# CanBus20mar.net
KiCad netlist of a schematic drawn in EAGLE
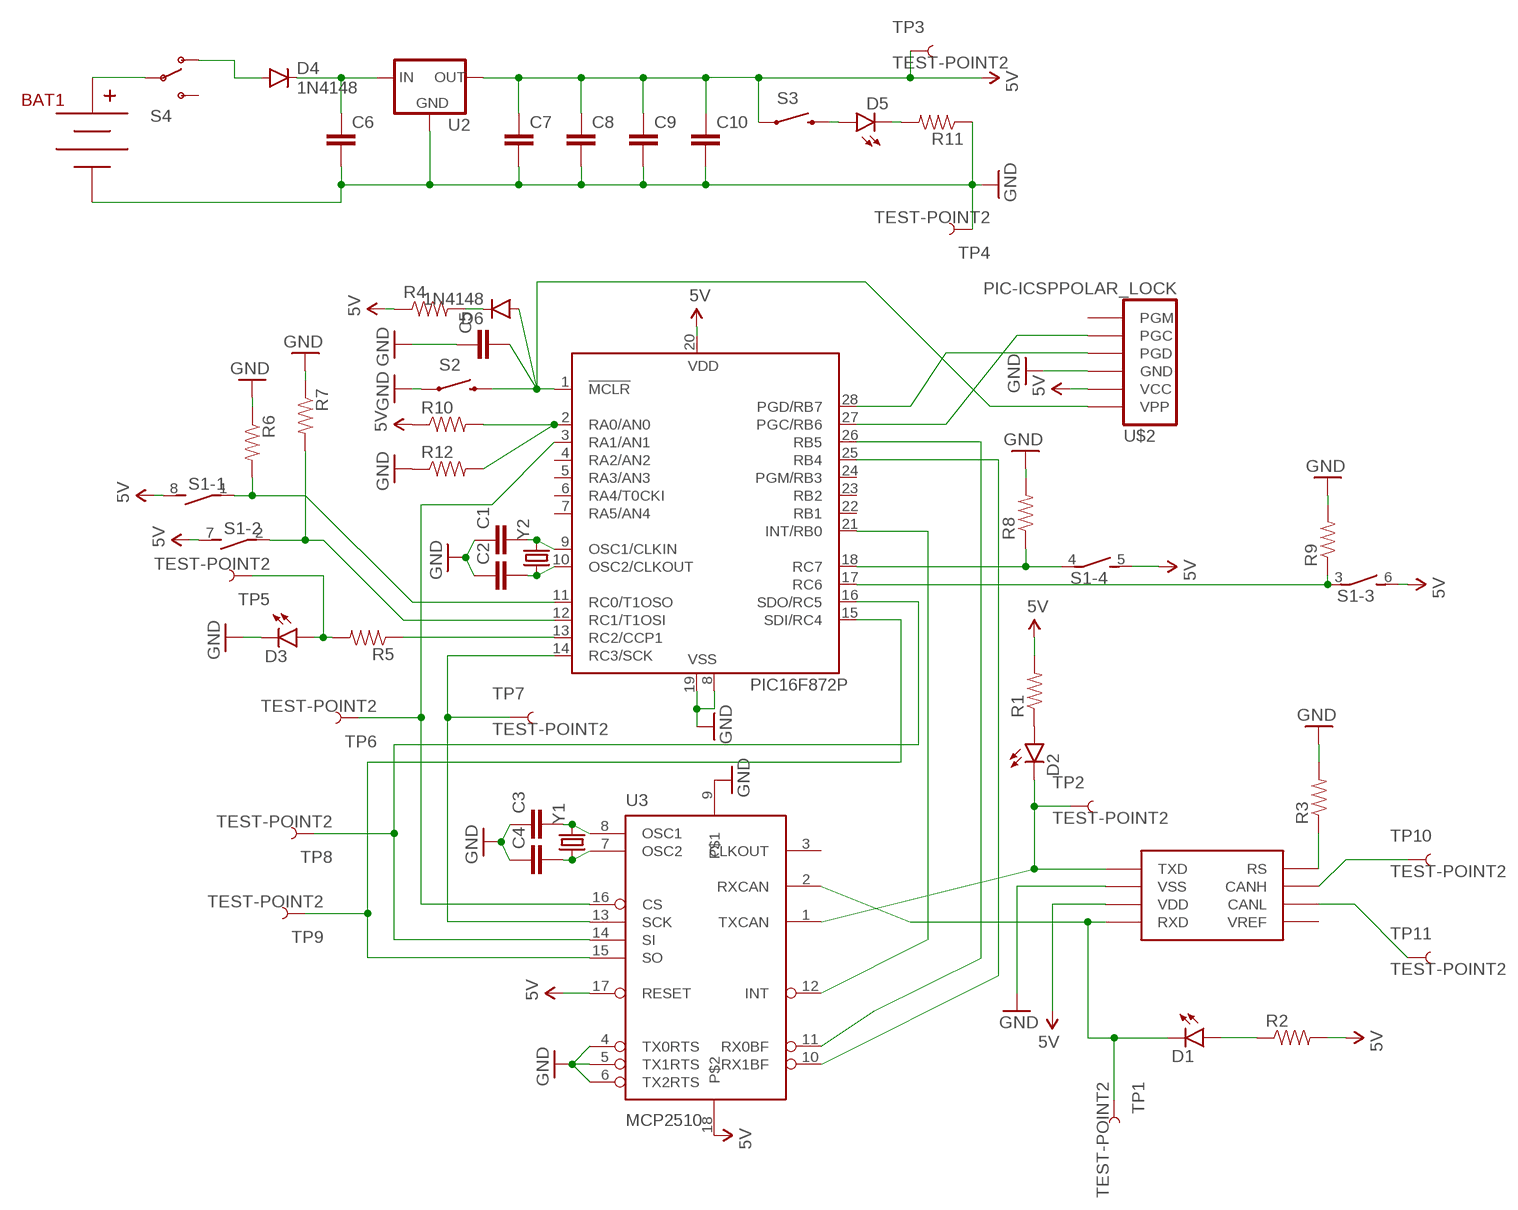
[diagram p0: schematic, sheet 1]

(export (version "E")
  (design (tool "Eeschema 10.0.6"))
  (components
    (comp (ref "BAT1")
      (value "BC9VPC")
      (footprint "eagle-import:BC9VPC")
      (libsource (lib "eagle-import") (part "BC9VPC"))
    )
    (comp (ref "C1")
      (value "CAPPTH")
      (footprint "eagle-import:CAP-PTH-SMALL")
      (libsource (lib "eagle-import") (part "CAPPTH"))
    )
    (comp (ref "C2")
      (value "CAPPTH")
      (footprint "eagle-import:CAP-PTH-SMALL")
      (libsource (lib "eagle-import") (part "CAPPTH"))
    )
    (comp (ref "C3")
      (value "CAPPTH")
      (footprint "eagle-import:CAP-PTH-SMALL")
      (libsource (lib "eagle-import") (part "CAPPTH"))
    )
    (comp (ref "C4")
      (value "CAPPTH")
      (footprint "eagle-import:CAP-PTH-SMALL")
      (libsource (lib "eagle-import") (part "CAPPTH"))
    )
    (comp (ref "C5")
      (value "CAPPTH")
      (footprint "eagle-import:CAP-PTH-SMALL")
      (libsource (lib "eagle-import") (part "CAPPTH"))
    )
    (comp (ref "C6")
      (value "CAPPTH")
      (footprint "eagle-import:CAP-PTH-SMALL")
      (libsource (lib "eagle-import") (part "CAPPTH"))
    )
    (comp (ref "C7")
      (value "CAPPTH")
      (footprint "eagle-import:CAP-PTH-SMALL")
      (libsource (lib "eagle-import") (part "CAPPTH"))
    )
    (comp (ref "C8")
      (value "CAPPTH")
      (footprint "eagle-import:CAP-PTH-SMALL")
      (libsource (lib "eagle-import") (part "CAPPTH"))
    )
    (comp (ref "C9")
      (value "CAPPTH")
      (footprint "eagle-import:CAP-PTH-SMALL")
      (libsource (lib "eagle-import") (part "CAPPTH"))
    )
    (comp (ref "C10")
      (value "CAPPTH")
      (footprint "eagle-import:CAP-PTH-SMALL")
      (libsource (lib "eagle-import") (part "CAPPTH"))
    )
    (comp (ref "D1")
      (value "LED5MM")
      (footprint "eagle-import:LED5MM")
      (libsource (lib "eagle-import") (part "LED5MM"))
    )
    (comp (ref "D2")
      (value "LED5MM")
      (footprint "eagle-import:LED5MM")
      (libsource (lib "eagle-import") (part "LED5MM"))
    )
    (comp (ref "D3")
      (value "LED5MM")
      (footprint "eagle-import:LED5MM")
      (libsource (lib "eagle-import") (part "LED5MM"))
    )
    (comp (ref "D4")
      (value "1N4148")
      (footprint "eagle-import:DIODE-1N4148-KIT")
      (libsource (lib "eagle-import") (part "DIODEKIT"))
    )
    (comp (ref "D5")
      (value "LED5MM")
      (footprint "eagle-import:LED5MM")
      (libsource (lib "eagle-import") (part "LED5MM"))
    )
    (comp (ref "D6")
      (value "1N4148")
      (footprint "eagle-import:DIODE-1N4148-KIT")
      (libsource (lib "eagle-import") (part "DIODEKIT"))
    )
    (comp (ref "IC1")
      (value "PIC16F872P")
      (footprint "eagle-import:DIL28-3")
      (fields (field (name "MF") "MICROCHIP") (field (name "MPN") "PIC16F872-I/SP"))
      (libsource (lib "eagle-import") (part "PIC16872PF"))
    )
    (comp (ref "R1")
      (value "RESISTOREZ")
      (footprint "eagle-import:AXIAL-0.3EZ")
      (libsource (lib "eagle-import") (part "RESISTOREZ"))
    )
    (comp (ref "R2")
      (value "RESISTOREZ")
      (footprint "eagle-import:AXIAL-0.3EZ")
      (libsource (lib "eagle-import") (part "RESISTOREZ"))
    )
    (comp (ref "R3")
      (value "RESISTOREZ")
      (footprint "eagle-import:AXIAL-0.3EZ")
      (libsource (lib "eagle-import") (part "RESISTOREZ"))
    )
    (comp (ref "R4")
      (value "RESISTOREZ")
      (footprint "eagle-import:AXIAL-0.3EZ")
      (libsource (lib "eagle-import") (part "RESISTOREZ"))
    )
    (comp (ref "R5")
      (value "RESISTOREZ")
      (footprint "eagle-import:AXIAL-0.3EZ")
      (libsource (lib "eagle-import") (part "RESISTOREZ"))
    )
    (comp (ref "R6")
      (value "RESISTOREZ")
      (footprint "eagle-import:AXIAL-0.3EZ")
      (libsource (lib "eagle-import") (part "RESISTOREZ"))
    )
    (comp (ref "R7")
      (value "RESISTOREZ")
      (footprint "eagle-import:AXIAL-0.3EZ")
      (libsource (lib "eagle-import") (part "RESISTOREZ"))
    )
    (comp (ref "R8")
      (value "RESISTOREZ")
      (footprint "eagle-import:AXIAL-0.3EZ")
      (libsource (lib "eagle-import") (part "RESISTOREZ"))
    )
    (comp (ref "R9")
      (value "RESISTOREZ")
      (footprint "eagle-import:AXIAL-0.3EZ")
      (libsource (lib "eagle-import") (part "RESISTOREZ"))
    )
    (comp (ref "R10")
      (value "RESISTOREZ")
      (footprint "eagle-import:AXIAL-0.3EZ")
      (libsource (lib "eagle-import") (part "RESISTOREZ"))
    )
    (comp (ref "R11")
      (value "RESISTOREZ")
      (footprint "eagle-import:AXIAL-0.3EZ")
      (libsource (lib "eagle-import") (part "RESISTOREZ"))
    )
    (comp (ref "R12")
      (value "RESISTORAXIAL-0.3")
      (footprint "eagle-import:AXIAL-0.3")
      (libsource (lib "eagle-import") (part "SparkFun-Resistors_RESISTORAXIAL-0.3"))
    )
    (comp (ref "S1")
      (value "DIP04S")
      (footprint "eagle-import:DIP04S")
      (libsource (lib "eagle-import") (part "DIP04S"))
    )
    (comp (ref "S2")
      (value "SWITCH-MOMENTARY-2PTH")
      (footprint "eagle-import:TACTILE-PTH")
      (libsource (lib "eagle-import") (part "SWITCH-MOMENTARY-2PTH"))
    )
    (comp (ref "S3")
      (value "SWITCH-MOMENTARY-2PTH")
      (footprint "eagle-import:TACTILE-PTH")
      (libsource (lib "eagle-import") (part "SWITCH-MOMENTARY-2PTH"))
    )
    (comp (ref "S4")
      (value "SWITCH-SPDTSMD2")
      (footprint "eagle-import:SWITCH-SPDT-SMD")
      (libsource (lib "eagle-import") (part "SWITCH-SPDTSMD2"))
    )
    (comp (ref "TP1")
      (value "TEST-POINT2")
      (footprint "eagle-import:PAD.02X.02")
      (libsource (lib "eagle-import") (part "TEST-POINT2"))
    )
    (comp (ref "TP2")
      (value "TEST-POINT2")
      (footprint "eagle-import:PAD.02X.02")
      (libsource (lib "eagle-import") (part "TEST-POINT2"))
    )
    (comp (ref "TP3")
      (value "TEST-POINT2")
      (footprint "eagle-import:PAD.02X.02")
      (libsource (lib "eagle-import") (part "TEST-POINT2"))
    )
    (comp (ref "TP4")
      (value "TEST-POINT2")
      (footprint "eagle-import:PAD.02X.02")
      (libsource (lib "eagle-import") (part "TEST-POINT2"))
    )
    (comp (ref "TP5")
      (value "TEST-POINT2")
      (footprint "eagle-import:PAD.02X.02")
      (libsource (lib "eagle-import") (part "TEST-POINT2"))
    )
    (comp (ref "TP6")
      (value "TEST-POINT2")
      (footprint "eagle-import:PAD.02X.02")
      (libsource (lib "eagle-import") (part "TEST-POINT2"))
    )
    (comp (ref "TP7")
      (value "TEST-POINT2")
      (footprint "eagle-import:PAD.02X.02")
      (libsource (lib "eagle-import") (part "TEST-POINT2"))
    )
    (comp (ref "TP8")
      (value "TEST-POINT2")
      (footprint "eagle-import:PAD.02X.02")
      (libsource (lib "eagle-import") (part "TEST-POINT2"))
    )
    (comp (ref "TP9")
      (value "TEST-POINT2")
      (footprint "eagle-import:PAD.02X.02")
      (libsource (lib "eagle-import") (part "TEST-POINT2"))
    )
    (comp (ref "TP10")
      (value "TEST-POINT2")
      (footprint "eagle-import:PAD.02X.02")
      (libsource (lib "eagle-import") (part "TEST-POINT2"))
    )
    (comp (ref "TP11")
      (value "TEST-POINT2")
      (footprint "eagle-import:PAD.02X.02")
      (libsource (lib "eagle-import") (part "TEST-POINT2"))
    )
    (comp (ref "U$1")
      (value "MCP2551")
      (footprint "eagle-import:MCP2551")
      (libsource (lib "eagle-import") (part "MCP2551"))
    )
    (comp (ref "U$2")
      (value "PIC-ICSPPOLAR_LOCK")
      (footprint "eagle-import:MOLEX-1X6_LOCK")
      (libsource (lib "eagle-import") (part "PIC-ICSPPOLAR_LOCK"))
    )
    (comp (ref "U2")
      (value "V_REG_78XXSIDE")
      (footprint "eagle-import:78XXL")
      (libsource (lib "eagle-import") (part "V_REG_78XXSIDE"))
    )
    (comp (ref "U3")
      (value "MCP2510")
      (footprint "eagle-import:DIL18")
      (libsource (lib "eagle-import") (part "MCP2510"))
    )
    (comp (ref "Y1")
      (value "CRYSTALHC49UV")
      (footprint "eagle-import:HC49U-V")
      (libsource (lib "eagle-import") (part "CRYSTALHC49UV"))
    )
    (comp (ref "Y2")
      (value "CRYSTALHC49UV")
      (footprint "eagle-import:HC49U-V")
      (libsource (lib "eagle-import") (part "CRYSTALHC49UV"))
    )
  )
  (nets
    (net (code "1") (name "5V") (class "Default")
      (node (ref "C10") (pin "1") (pinfunction "1_1") (pintype "passive"))
      (node (ref "C7") (pin "1") (pinfunction "1_1") (pintype "passive"))
      (node (ref "C8") (pin "1") (pinfunction "1_1") (pintype "passive"))
      (node (ref "C9") (pin "1") (pinfunction "1_1") (pintype "passive"))
      (node (ref "IC1") (pin "20") (pinfunction "VDD_20") (pintype "power_in"))
      (node (ref "R1") (pin "P$2") (pinfunction "2_P$2") (pintype "passive"))
      (node (ref "R10") (pin "P$1") (pinfunction "1_P$1") (pintype "passive"))
      (node (ref "R2") (pin "P$2") (pinfunction "2_P$2") (pintype "passive"))
      (node (ref "R4") (pin "P$1") (pinfunction "1_P$1") (pintype "passive"))
      (node (ref "S1") (pin "5") (pinfunction "2_5") (pintype "passive"))
      (node (ref "S1") (pin "6") (pinfunction "2_6") (pintype "passive"))
      (node (ref "S1") (pin "7") (pinfunction "2_7") (pintype "passive"))
      (node (ref "S1") (pin "8") (pinfunction "2_8") (pintype "passive"))
      (node (ref "S3") (pin "1") (pinfunction "1_1") (pintype "passive"))
      (node (ref "TP3") (pin "P$1") (pinfunction "1_P$1") (pintype "bidirectional"))
      (node (ref "U$1") (pin "VDD") (pinfunction "VDD_VDD") (pintype "bidirectional"))
      (node (ref "U$2") (pin "5") (pinfunction "VCC_5") (pintype "bidirectional"))
      (node (ref "U2") (pin "OUT") (pinfunction "OUT_OUT") (pintype "passive"))
      (node (ref "U3") (pin "17") (pinfunction "RESET_17") (pintype "input"))
      (node (ref "U3") (pin "18") (pinfunction "P$2_18") (pintype "bidirectional"))
    )
    (net (code "2") (name "GND") (class "Default")
      (node (ref "BAT1") (pin "V-") (pinfunction "V-_V-") (pintype "bidirectional"))
      (node (ref "C1") (pin "1") (pinfunction "1_1") (pintype "passive"))
      (node (ref "C10") (pin "2") (pinfunction "2_2") (pintype "passive"))
      (node (ref "C2") (pin "1") (pinfunction "1_1") (pintype "passive"))
      (node (ref "C3") (pin "1") (pinfunction "1_1") (pintype "passive"))
      (node (ref "C4") (pin "1") (pinfunction "1_1") (pintype "passive"))
      (node (ref "C5") (pin "1") (pinfunction "1_1") (pintype "passive"))
      (node (ref "C6") (pin "2") (pinfunction "2_2") (pintype "passive"))
      (node (ref "C7") (pin "2") (pinfunction "2_2") (pintype "passive"))
      (node (ref "C8") (pin "2") (pinfunction "2_2") (pintype "passive"))
      (node (ref "C9") (pin "2") (pinfunction "2_2") (pintype "passive"))
      (node (ref "D3") (pin "K") (pinfunction "C_K") (pintype "passive"))
      (node (ref "IC1") (pin "19") (pinfunction "VSS_19") (pintype "power_in"))
      (node (ref "IC1") (pin "8") (pinfunction "VSS_8") (pintype "power_in"))
      (node (ref "R11") (pin "P$1") (pinfunction "1_P$1") (pintype "passive"))
      (node (ref "R12") (pin "P$1") (pinfunction "1_P$1") (pintype "passive"))
      (node (ref "R3") (pin "P$2") (pinfunction "2_P$2") (pintype "passive"))
      (node (ref "R6") (pin "P$1") (pinfunction "1_P$1") (pintype "passive"))
      (node (ref "R7") (pin "P$1") (pinfunction "1_P$1") (pintype "passive"))
      (node (ref "R8") (pin "P$2") (pinfunction "2_P$2") (pintype "passive"))
      (node (ref "R9") (pin "P$2") (pinfunction "2_P$2") (pintype "passive"))
      (node (ref "S2") (pin "1") (pinfunction "1_1") (pintype "passive"))
      (node (ref "TP4") (pin "P$1") (pinfunction "1_P$1") (pintype "bidirectional"))
      (node (ref "U$1") (pin "VSS") (pinfunction "VSS_VSS") (pintype "bidirectional"))
      (node (ref "U$2") (pin "4") (pinfunction "GND_4") (pintype "bidirectional"))
      (node (ref "U2") (pin "GND") (pinfunction "GND_GND") (pintype "input"))
      (node (ref "U3") (pin "4") (pinfunction "TX0RTS_4") (pintype "input"))
      (node (ref "U3") (pin "5") (pinfunction "TX1RTS_5") (pintype "input"))
      (node (ref "U3") (pin "6") (pinfunction "TX2RTS_6") (pintype "input"))
      (node (ref "U3") (pin "9") (pinfunction "P$1_9") (pintype "bidirectional"))
    )
    (net (code "3") (name "Net-(C6-Pad1)") (class "Default")
      (node (ref "C6") (pin "1") (pinfunction "1_1") (pintype "passive"))
      (node (ref "D4") (pin "C") (pinfunction "C_C") (pintype "passive"))
      (node (ref "U2") (pin "IN") (pinfunction "IN_IN") (pintype "input"))
    )
    (net (code "4") (name "Net-(D1-C)") (class "Default")
      (node (ref "D1") (pin "K") (pinfunction "C_K") (pintype "passive"))
      (node (ref "TP1") (pin "P$1") (pinfunction "1_P$1") (pintype "bidirectional"))
      (node (ref "U$1") (pin "RXD") (pinfunction "RXD_RXD") (pintype "bidirectional"))
      (node (ref "U3") (pin "2") (pinfunction "RXCAN_2") (pintype "input"))
    )
    (net (code "5") (name "Net-(D2-C)") (class "Default")
      (node (ref "D2") (pin "K") (pinfunction "C_K") (pintype "passive"))
      (node (ref "TP2") (pin "P$1") (pinfunction "1_P$1") (pintype "bidirectional"))
      (node (ref "U$1") (pin "TXD") (pinfunction "TXD_TXD") (pintype "bidirectional"))
      (node (ref "U3") (pin "1") (pinfunction "TXCAN_1") (pintype "output"))
    )
    (net (code "6") (name "Net-(D5-C)") (class "Default")
      (node (ref "D5") (pin "K") (pinfunction "C_K") (pintype "passive"))
      (node (ref "R11") (pin "P$2") (pinfunction "2_P$2") (pintype "passive"))
    )
    (net (code "7") (name "Net-(IC1-INT{slash}RB0)") (class "Default")
      (node (ref "IC1") (pin "21") (pinfunction "INT/RB0_21") (pintype "bidirectional"))
      (node (ref "U3") (pin "12") (pinfunction "INT_12") (pintype "output"))
    )
    (net (code "8") (name "Net-(IC1-OSC1{slash}CLKIN)") (class "Default")
      (node (ref "C1") (pin "2") (pinfunction "2_2") (pintype "passive"))
      (node (ref "IC1") (pin "9") (pinfunction "OSC1/CLKIN_9") (pintype "input"))
      (node (ref "Y2") (pin "2") (pinfunction "2_2") (pintype "passive"))
    )
    (net (code "9") (name "Net-(IC1-OSC2{slash}CLKOUT)") (class "Default")
      (node (ref "C2") (pin "2") (pinfunction "2_2") (pintype "passive"))
      (node (ref "IC1") (pin "10") (pinfunction "OSC2/CLKOUT_10") (pintype "output"))
      (node (ref "Y2") (pin "1") (pinfunction "1_1") (pintype "passive"))
    )
    (net (code "10") (name "Net-(IC1-PGC{slash}RB6)") (class "Default")
      (node (ref "IC1") (pin "27") (pinfunction "PGC/RB6_27") (pintype "bidirectional"))
      (node (ref "U$2") (pin "2") (pinfunction "PGC_2") (pintype "bidirectional"))
    )
    (net (code "11") (name "Net-(IC1-PGD{slash}RB7)") (class "Default")
      (node (ref "IC1") (pin "28") (pinfunction "PGD/RB7_28") (pintype "bidirectional"))
      (node (ref "U$2") (pin "3") (pinfunction "PGD_3") (pintype "bidirectional"))
    )
    (net (code "12") (name "Net-(IC1-RA0{slash}AN0)") (class "Default")
      (node (ref "IC1") (pin "2") (pinfunction "RA0/AN0_2") (pintype "bidirectional"))
      (node (ref "R10") (pin "P$2") (pinfunction "2_P$2") (pintype "passive"))
      (node (ref "R12") (pin "P$2") (pinfunction "2_P$2") (pintype "passive"))
    )
    (net (code "13") (name "Net-(IC1-RA1{slash}AN1)") (class "Default")
      (node (ref "IC1") (pin "3") (pinfunction "RA1/AN1_3") (pintype "bidirectional"))
      (node (ref "TP6") (pin "P$1") (pinfunction "1_P$1") (pintype "bidirectional"))
      (node (ref "U3") (pin "16") (pinfunction "CS_16") (pintype "input"))
    )
    (net (code "14") (name "Net-(IC1-RB4)") (class "Default")
      (node (ref "IC1") (pin "25") (pinfunction "RB4_25") (pintype "bidirectional"))
      (node (ref "U3") (pin "10") (pinfunction "RX1BF_10") (pintype "output"))
    )
    (net (code "15") (name "Net-(IC1-RB5)") (class "Default")
      (node (ref "IC1") (pin "26") (pinfunction "RB5_26") (pintype "bidirectional"))
      (node (ref "U3") (pin "11") (pinfunction "RX0BF_11") (pintype "output"))
    )
    (net (code "16") (name "Net-(IC1-RC0{slash}T1OSO)") (class "Default")
      (node (ref "IC1") (pin "11") (pinfunction "RC0/T1OSO_11") (pintype "bidirectional"))
      (node (ref "R6") (pin "P$2") (pinfunction "2_P$2") (pintype "passive"))
      (node (ref "S1") (pin "1") (pinfunction "1_1") (pintype "passive"))
    )
    (net (code "17") (name "Net-(IC1-RC1{slash}T1OSI)") (class "Default")
      (node (ref "IC1") (pin "12") (pinfunction "RC1/T1OSI_12") (pintype "bidirectional"))
      (node (ref "R7") (pin "P$2") (pinfunction "2_P$2") (pintype "passive"))
      (node (ref "S1") (pin "2") (pinfunction "1_2") (pintype "passive"))
    )
    (net (code "18") (name "Net-(IC1-RC2{slash}CCP1)") (class "Default")
      (node (ref "IC1") (pin "13") (pinfunction "RC2/CCP1_13") (pintype "bidirectional"))
      (node (ref "R5") (pin "P$1") (pinfunction "1_P$1") (pintype "passive"))
    )
    (net (code "19") (name "Net-(IC1-RC3{slash}SCK)") (class "Default")
      (node (ref "IC1") (pin "14") (pinfunction "RC3/SCK_14") (pintype "bidirectional"))
      (node (ref "TP7") (pin "P$1") (pinfunction "1_P$1") (pintype "bidirectional"))
      (node (ref "U3") (pin "13") (pinfunction "SCK_13") (pintype "input"))
    )
    (net (code "20") (name "Net-(IC1-RC6)") (class "Default")
      (node (ref "IC1") (pin "17") (pinfunction "RC6_17") (pintype "bidirectional"))
      (node (ref "R9") (pin "P$1") (pinfunction "1_P$1") (pintype "passive"))
      (node (ref "S1") (pin "3") (pinfunction "1_3") (pintype "passive"))
    )
    (net (code "21") (name "Net-(IC1-RC7)") (class "Default")
      (node (ref "IC1") (pin "18") (pinfunction "RC7_18") (pintype "bidirectional"))
      (node (ref "R8") (pin "P$1") (pinfunction "1_P$1") (pintype "passive"))
      (node (ref "S1") (pin "4") (pinfunction "1_4") (pintype "passive"))
    )
    (net (code "22") (name "Net-(IC1-SDI{slash}RC4)") (class "Default")
      (node (ref "IC1") (pin "15") (pinfunction "SDI/RC4_15") (pintype "bidirectional"))
      (node (ref "TP9") (pin "P$1") (pinfunction "1_P$1") (pintype "bidirectional"))
      (node (ref "U3") (pin "15") (pinfunction "SO_15") (pintype "output"))
    )
    (net (code "23") (name "Net-(IC1-SDO{slash}RC5)") (class "Default")
      (node (ref "IC1") (pin "16") (pinfunction "SDO/RC5_16") (pintype "bidirectional"))
      (node (ref "TP8") (pin "P$1") (pinfunction "1_P$1") (pintype "bidirectional"))
      (node (ref "U3") (pin "14") (pinfunction "SI_14") (pintype "input"))
    )
    (net (code "24") (name "Net-(IC1-~{MCLR})") (class "Default")
      (node (ref "C5") (pin "2") (pinfunction "2_2") (pintype "passive"))
      (node (ref "D6") (pin "A") (pinfunction "A_A") (pintype "passive"))
      (node (ref "IC1") (pin "1") (pinfunction "~{MCLR}_1") (pintype "input"))
      (node (ref "S2") (pin "3") (pinfunction "2_3") (pintype "passive"))
      (node (ref "U$2") (pin "6") (pinfunction "VPP_6") (pintype "bidirectional"))
    )
    (net (code "25") (name "Net-(R1-1)") (class "Default")
      (node (ref "D2") (pin "A") (pinfunction "A_A") (pintype "passive"))
      (node (ref "R1") (pin "P$1") (pinfunction "1_P$1") (pintype "passive"))
    )
    (net (code "26") (name "Net-(R2-1)") (class "Default")
      (node (ref "D1") (pin "A") (pinfunction "A_A") (pintype "passive"))
      (node (ref "R2") (pin "P$1") (pinfunction "1_P$1") (pintype "passive"))
    )
    (net (code "27") (name "Net-(R3-1)") (class "Default")
      (node (ref "R3") (pin "P$1") (pinfunction "1_P$1") (pintype "passive"))
      (node (ref "U$1") (pin "RS") (pinfunction "RS_RS") (pintype "bidirectional"))
    )
    (net (code "28") (name "Net-(R4-2)") (class "Default")
      (node (ref "D6") (pin "C") (pinfunction "C_C") (pintype "passive"))
      (node (ref "R4") (pin "P$2") (pinfunction "2_P$2") (pintype "passive"))
    )
    (net (code "29") (name "Net-(R5-2)") (class "Default")
      (node (ref "D3") (pin "A") (pinfunction "A_A") (pintype "passive"))
      (node (ref "R5") (pin "P$2") (pinfunction "2_P$2") (pintype "passive"))
      (node (ref "TP5") (pin "P$1") (pinfunction "1_P$1") (pintype "bidirectional"))
    )
    (net (code "30") (name "Net-(S3-2)") (class "Default")
      (node (ref "D5") (pin "A") (pinfunction "A_A") (pintype "passive"))
      (node (ref "S3") (pin "3") (pinfunction "2_3") (pintype "passive"))
    )
    (net (code "31") (name "Net-(S4-O)") (class "Default")
      (node (ref "D4") (pin "A") (pinfunction "A_A") (pintype "passive"))
      (node (ref "S4") (pin "1") (pinfunction "O_1") (pintype "passive"))
    )
    (net (code "32") (name "Net-(S4-P)") (class "Default")
      (node (ref "BAT1") (pin "V+") (pinfunction "V+_V+") (pintype "bidirectional"))
      (node (ref "S4") (pin "2") (pinfunction "P_2") (pintype "passive"))
    )
    (net (code "33") (name "Net-(TP10-1)") (class "Default")
      (node (ref "TP10") (pin "P$1") (pinfunction "1_P$1") (pintype "bidirectional"))
      (node (ref "U$1") (pin "CANH") (pinfunction "CANH_CANH") (pintype "bidirectional"))
    )
    (net (code "34") (name "Net-(TP11-1)") (class "Default")
      (node (ref "TP11") (pin "P$1") (pinfunction "1_P$1") (pintype "bidirectional"))
      (node (ref "U$1") (pin "CANL") (pinfunction "CANL_CANL") (pintype "bidirectional"))
    )
    (net (code "35") (name "Net-(U3-OSC1)") (class "Default")
      (node (ref "C3") (pin "2") (pinfunction "2_2") (pintype "passive"))
      (node (ref "U3") (pin "8") (pinfunction "OSC1_8") (pintype "input"))
      (node (ref "Y1") (pin "2") (pinfunction "2_2") (pintype "passive"))
    )
    (net (code "36") (name "Net-(U3-OSC2)") (class "Default")
      (node (ref "C4") (pin "2") (pinfunction "2_2") (pintype "passive"))
      (node (ref "U3") (pin "7") (pinfunction "OSC2_7") (pintype "output"))
      (node (ref "Y1") (pin "1") (pinfunction "1_1") (pintype "passive"))
    )
    (net (code "37") (name "unconnected-(IC1-PGM{slash}RB3-Pad24)") (class "Default")
      (node (ref "IC1") (pin "24") (pinfunction "PGM/RB3_24") (pintype "bidirectional"))
    )
    (net (code "38") (name "unconnected-(IC1-RA2{slash}AN2-Pad4)") (class "Default")
      (node (ref "IC1") (pin "4") (pinfunction "RA2/AN2_4") (pintype "bidirectional"))
    )
    (net (code "39") (name "unconnected-(IC1-RA3{slash}AN3-Pad5)") (class "Default")
      (node (ref "IC1") (pin "5") (pinfunction "RA3/AN3_5") (pintype "bidirectional"))
    )
    (net (code "40") (name "unconnected-(IC1-RA4{slash}T0CKI-Pad6)") (class "Default")
      (node (ref "IC1") (pin "6") (pinfunction "RA4/T0CKI_6") (pintype "bidirectional"))
    )
    (net (code "41") (name "unconnected-(IC1-RA5{slash}AN4-Pad7)") (class "Default")
      (node (ref "IC1") (pin "7") (pinfunction "RA5/AN4_7") (pintype "bidirectional"))
    )
    (net (code "42") (name "unconnected-(IC1-RB1-Pad22)") (class "Default")
      (node (ref "IC1") (pin "22") (pinfunction "RB1_22") (pintype "bidirectional"))
    )
    (net (code "43") (name "unconnected-(IC1-RB2-Pad23)") (class "Default")
      (node (ref "IC1") (pin "23") (pinfunction "RB2_23") (pintype "bidirectional"))
    )
    (net (code "44") (name "unconnected-(S4-S-Pad3)") (class "Default")
      (node (ref "S4") (pin "3") (pinfunction "S_3") (pintype "passive"))
    )
    (net (code "45") (name "unconnected-(U$1-PadVREF)") (class "Default")
      (node (ref "U$1") (pin "VREF") (pinfunction "VREF_VREF") (pintype "bidirectional"))
    )
    (net (code "46") (name "unconnected-(U$2-PGM-Pad1)") (class "Default")
      (node (ref "U$2") (pin "1") (pinfunction "PGM_1") (pintype "bidirectional"))
    )
    (net (code "47") (name "unconnected-(U3-CLKOUT-Pad3)") (class "Default")
      (node (ref "U3") (pin "3") (pinfunction "CLKOUT_3") (pintype "output"))
    )
  )
)
